# GaN_Driver.net
KiCad netlist of a schematic drawn in Altium Designer
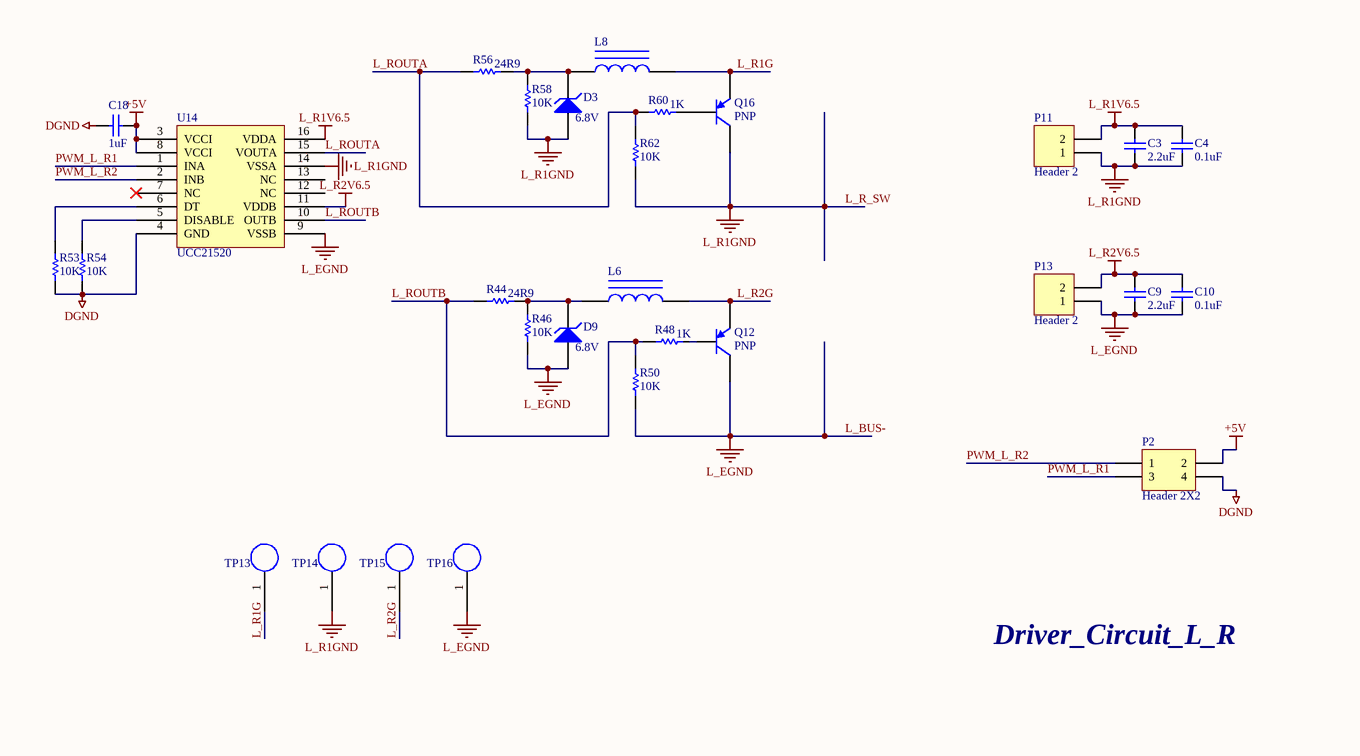
[diagram p0: GaN_Driver.SchDoc, left]

(export (version "E")
  (design (tool "Eeschema 10.0.6"))
  (components
    (comp (ref "C3")
      (value "2.2uF")
      (footprint "0603_C")
      (description "Capacitor")
      (fields
        (field (name "MANUFACTURER") "Generic Components")
        (field (name "PUBLISHER") "Altium Hobart Technology Centre")
      )
      (libsource (lib "Miscellaneous Devices") (part "Cap"))
    )
    (comp (ref "C4")
      (value "0.1uF")
      (footprint "0603_C")
      (description "Capacitor")
      (fields
        (field (name "MANUFACTURER") "Generic Components")
        (field (name "PUBLISHER") "Altium Hobart Technology Centre")
      )
      (libsource (lib "Miscellaneous Devices") (part "Cap"))
    )
    (comp (ref "C9")
      (value "2.2uF")
      (footprint "0603_C")
      (description "Capacitor")
      (fields
        (field (name "MANUFACTURER") "Generic Components")
        (field (name "PUBLISHER") "Altium Hobart Technology Centre")
      )
      (libsource (lib "Miscellaneous Devices") (part "Cap"))
    )
    (comp (ref "C10")
      (value "0.1uF")
      (footprint "0603_C")
      (description "Capacitor")
      (fields
        (field (name "MANUFACTURER") "Generic Components")
        (field (name "PUBLISHER") "Altium Hobart Technology Centre")
      )
      (libsource (lib "Miscellaneous Devices") (part "Cap"))
    )
    (comp (ref "C18")
      (value "1uF")
      (footprint "0603_C")
      (description "Capacitor")
      (fields
        (field (name "MANUFACTURER") "Generic Components")
        (field (name "PUBLISHER") "Altium Hobart Technology Centre")
      )
      (libsource (lib "Miscellaneous Devices") (part "Cap"))
    )
    (comp (ref "D3")
      (value "6.8V")
      (footprint "SOD323")
      (description "Zener Diode")
      (fields (field (name "PUBLISHER") "Altium Limited"))
      (libsource (lib "Miscellaneous Devices") (part "D Zener"))
    )
    (comp (ref "D9")
      (value "6.8V")
      (footprint "SOD323")
      (description "Zener Diode")
      (fields (field (name "PUBLISHER") "Altium Limited"))
      (libsource (lib "Miscellaneous Devices") (part "D Zener"))
    )
    (comp (ref "L6")
      (value "Inductor Iron")
      (footprint "0603_R")
      (description "Magnetic-Core Inductor")
      (fields (field (name "PUBLISHER") "Altium Limited"))
      (libsource (lib "Miscellaneous Devices") (part "Inductor Iron"))
    )
    (comp (ref "L8")
      (value "Inductor Iron")
      (footprint "0603_R")
      (description "Magnetic-Core Inductor")
      (fields (field (name "PUBLISHER") "Altium Limited"))
      (libsource (lib "Miscellaneous Devices") (part "Inductor Iron"))
    )
    (comp (ref "P2")
      (value "Header 2X2")
      (footprint "HDR2X2")
      (description "Header, 2-Pin, Dual row")
      (fields (field (name "PUBLISHER") "Altium Limited"))
      (libsource (lib "Miscellaneous Connectors") (part "Header 2X2"))
    )
    (comp (ref "P11")
      (value "Header 2")
      (footprint "HDR1X2")
      (description "Header, 2-Pin")
      (fields (field (name "PUBLISHER") "Altium Limited"))
      (libsource (lib "Miscellaneous Connectors") (part "Header 2"))
    )
    (comp (ref "P13")
      (value "Header 2")
      (footprint "HDR1X2")
      (description "Header, 2-Pin")
      (fields (field (name "PUBLISHER") "Altium Limited"))
      (libsource (lib "Miscellaneous Connectors") (part "Header 2"))
    )
    (comp (ref "Q12")
      (value "PNP")
      (footprint "SOT-23 (NPN/PNP)")
      (description "PNP Bipolar Transistor")
      (fields (field (name "PUBLISHER") "Altium Limited"))
      (libsource (lib "Miscellaneous Devices") (part "PNP"))
    )
    (comp (ref "Q16")
      (value "PNP")
      (footprint "SOT-23 (NPN/PNP)")
      (description "PNP Bipolar Transistor")
      (fields (field (name "PUBLISHER") "Altium Limited"))
      (libsource (lib "Miscellaneous Devices") (part "PNP"))
    )
    (comp (ref "R44")
      (value "24R9")
      (footprint "0603_R")
      (description "Semiconductor Resistor")
      (fields (field (name "PUBLISHER") "Altium Limited"))
      (libsource (lib "Miscellaneous Devices") (part "Res Semi"))
    )
    (comp (ref "R46")
      (value "10K")
      (footprint "0603_R")
      (description "Semiconductor Resistor")
      (fields (field (name "PUBLISHER") "Altium Limited"))
      (libsource (lib "Miscellaneous Devices") (part "Res Semi"))
    )
    (comp (ref "R48")
      (value "1K")
      (footprint "0603_R")
      (description "Semiconductor Resistor")
      (fields (field (name "Comment") "1k") (field (name "PUBLISHER") "Altium Limited"))
      (libsource (lib "Miscellaneous Devices") (part "Res Semi"))
    )
    (comp (ref "R50")
      (value "10K")
      (footprint "0603_R")
      (description "Semiconductor Resistor")
      (fields (field (name "PUBLISHER") "Altium Limited"))
      (libsource (lib "Miscellaneous Devices") (part "Res Semi"))
    )
    (comp (ref "R53")
      (value "10K")
      (footprint "0603_R")
      (description "Semiconductor Resistor")
      (fields (field (name "PUBLISHER") "Altium Limited"))
      (libsource (lib "Miscellaneous Devices") (part "Res Semi"))
    )
    (comp (ref "R54")
      (value "10K")
      (footprint "0603_R")
      (description "Semiconductor Resistor")
      (fields (field (name "PUBLISHER") "Altium Limited"))
      (libsource (lib "Miscellaneous Devices") (part "Res Semi"))
    )
    (comp (ref "R56")
      (value "24R9")
      (footprint "0603_R")
      (description "Semiconductor Resistor")
      (fields (field (name "PUBLISHER") "Altium Limited"))
      (libsource (lib "Miscellaneous Devices") (part "Res Semi"))
    )
    (comp (ref "R58")
      (value "10K")
      (footprint "0603_R")
      (description "Semiconductor Resistor")
      (fields (field (name "PUBLISHER") "Altium Limited"))
      (libsource (lib "Miscellaneous Devices") (part "Res Semi"))
    )
    (comp (ref "R60")
      (value "1K")
      (footprint "0603_R")
      (description "Semiconductor Resistor")
      (fields (field (name "Comment") "1k") (field (name "PUBLISHER") "Altium Limited"))
      (libsource (lib "Miscellaneous Devices") (part "Res Semi"))
    )
    (comp (ref "R62")
      (value "10K")
      (footprint "0603_R")
      (description "Semiconductor Resistor")
      (fields (field (name "PUBLISHER") "Altium Limited"))
      (libsource (lib "Miscellaneous Devices") (part "Res Semi"))
    )
    (comp (ref "TP13")
      (value "Test_Point")
      (footprint "Test_Point")
      (libsource (lib "GaN_Half_Bridge") (part "Test_Point"))
    )
    (comp (ref "TP14")
      (value "Test_Point")
      (footprint "Test_Point")
      (libsource (lib "GaN_Half_Bridge") (part "Test_Point"))
    )
    (comp (ref "TP15")
      (value "Test_Point")
      (footprint "Test_Point")
      (libsource (lib "GaN_Half_Bridge") (part "Test_Point"))
    )
    (comp (ref "TP16")
      (value "Test_Point")
      (footprint "Test_Point")
      (libsource (lib "GaN_Half_Bridge") (part "Test_Point"))
    )
    (comp (ref "U14")
      (value "UCC21520")
      (footprint "SOIC-16W")
      (libsource (lib "Schlib_LZW") (part "UCC21520"))
    )
  )
  (nets
    (net (code "1") (name "+5V") (class "Default")
      (node (ref "C18") (pin "1") (pinfunction "1_1") (pintype "passive"))
      (node (ref "P2") (pin "2") (pinfunction "2_2") (pintype "passive"))
      (node (ref "U14") (pin "3") (pinfunction "VCCI_3") (pintype "passive"))
      (node (ref "U14") (pin "8") (pinfunction "VCCI_8") (pintype "passive"))
    )
    (net (code "2") (name "/L_R1G") (class "Default")
      (node (ref "L8") (pin "2") (pinfunction "2_2") (pintype "passive"))
      (node (ref "Q16") (pin "3") (pinfunction "E_3") (pintype "passive"))
      (node (ref "TP13") (pin "1") (pinfunction "1_1") (pintype "passive"))
    )
    (net (code "3") (name "/L_R2G") (class "Default")
      (node (ref "L6") (pin "2") (pinfunction "2_2") (pintype "passive"))
      (node (ref "Q12") (pin "3") (pinfunction "E_3") (pintype "passive"))
      (node (ref "TP15") (pin "1") (pinfunction "1_1") (pintype "passive"))
    )
    (net (code "4") (name "/L_ROUTA") (class "Default")
      (node (ref "R56") (pin "1") (pinfunction "1_1") (pintype "passive"))
      (node (ref "R60") (pin "1") (pinfunction "1_1") (pintype "passive"))
      (node (ref "R62") (pin "2") (pinfunction "2_2") (pintype "passive"))
      (node (ref "U14") (pin "15") (pinfunction "VOUTA_15") (pintype "passive"))
    )
    (net (code "5") (name "/L_ROUTB") (class "Default")
      (node (ref "R44") (pin "1") (pinfunction "1_1") (pintype "passive"))
      (node (ref "R48") (pin "1") (pinfunction "1_1") (pintype "passive"))
      (node (ref "R50") (pin "2") (pinfunction "2_2") (pintype "passive"))
      (node (ref "U14") (pin "10") (pinfunction "OUTB_10") (pintype "passive"))
    )
    (net (code "6") (name "/PWM_L_R1") (class "Default")
      (node (ref "P2") (pin "3") (pinfunction "3_3") (pintype "passive"))
      (node (ref "U14") (pin "1") (pinfunction "INA_1") (pintype "passive"))
    )
    (net (code "7") (name "/PWM_L_R2") (class "Default")
      (node (ref "P2") (pin "1") (pinfunction "1_1") (pintype "passive"))
      (node (ref "U14") (pin "2") (pinfunction "INB_2") (pintype "passive"))
    )
    (net (code "8") (name "DGND") (class "Default")
      (node (ref "C18") (pin "2") (pinfunction "2_2") (pintype "passive"))
      (node (ref "P2") (pin "4") (pinfunction "4_4") (pintype "passive"))
      (node (ref "R53") (pin "1") (pinfunction "1_1") (pintype "passive"))
      (node (ref "R54") (pin "1") (pinfunction "1_1") (pintype "passive"))
      (node (ref "U14") (pin "4") (pinfunction "GND_4") (pintype "passive"))
    )
    (net (code "9") (name "L_EGND") (class "Default")
      (node (ref "C10") (pin "2") (pinfunction "2_2") (pintype "passive"))
      (node (ref "C9") (pin "2") (pinfunction "2_2") (pintype "passive"))
      (node (ref "D9") (pin "1") (pinfunction "A_1") (pintype "passive"))
      (node (ref "P13") (pin "1") (pinfunction "1_1") (pintype "passive"))
      (node (ref "Q12") (pin "1") (pinfunction "C_1") (pintype "passive"))
      (node (ref "R46") (pin "1") (pinfunction "1_1") (pintype "passive"))
      (node (ref "R50") (pin "1") (pinfunction "1_1") (pintype "passive"))
      (node (ref "TP16") (pin "1") (pinfunction "1_1") (pintype "passive"))
      (node (ref "U14") (pin "9") (pinfunction "VSSB_9") (pintype "passive"))
    )
    (net (code "10") (name "L_R1GND") (class "Default")
      (node (ref "C3") (pin "2") (pinfunction "2_2") (pintype "passive"))
      (node (ref "C4") (pin "2") (pinfunction "2_2") (pintype "passive"))
      (node (ref "D3") (pin "1") (pinfunction "A_1") (pintype "passive"))
      (node (ref "P11") (pin "1") (pinfunction "1_1") (pintype "passive"))
      (node (ref "Q16") (pin "1") (pinfunction "C_1") (pintype "passive"))
      (node (ref "R58") (pin "1") (pinfunction "1_1") (pintype "passive"))
      (node (ref "R62") (pin "1") (pinfunction "1_1") (pintype "passive"))
      (node (ref "TP14") (pin "1") (pinfunction "1_1") (pintype "passive"))
      (node (ref "U14") (pin "14") (pinfunction "VSSA_14") (pintype "passive"))
    )
    (net (code "11") (name "L_R1V6.5") (class "Default")
      (node (ref "C3") (pin "1") (pinfunction "1_1") (pintype "passive"))
      (node (ref "C4") (pin "1") (pinfunction "1_1") (pintype "passive"))
      (node (ref "P11") (pin "2") (pinfunction "2_2") (pintype "passive"))
      (node (ref "U14") (pin "16") (pinfunction "VDDA_16") (pintype "passive"))
    )
    (net (code "12") (name "L_R2V6.5") (class "Default")
      (node (ref "C10") (pin "1") (pinfunction "1_1") (pintype "passive"))
      (node (ref "C9") (pin "1") (pinfunction "1_1") (pintype "passive"))
      (node (ref "P13") (pin "2") (pinfunction "2_2") (pintype "passive"))
      (node (ref "U14") (pin "11") (pinfunction "VDDB_11") (pintype "passive"))
    )
    (net (code "13") (name "Net-(D3-K)") (class "Default")
      (node (ref "D3") (pin "2") (pinfunction "K_2") (pintype "passive"))
      (node (ref "L8") (pin "1") (pinfunction "1_1") (pintype "passive"))
      (node (ref "R56") (pin "2") (pinfunction "2_2") (pintype "passive"))
      (node (ref "R58") (pin "2") (pinfunction "2_2") (pintype "passive"))
    )
    (net (code "14") (name "Net-(D9-K)") (class "Default")
      (node (ref "D9") (pin "2") (pinfunction "K_2") (pintype "passive"))
      (node (ref "L6") (pin "1") (pinfunction "1_1") (pintype "passive"))
      (node (ref "R44") (pin "2") (pinfunction "2_2") (pintype "passive"))
      (node (ref "R46") (pin "2") (pinfunction "2_2") (pintype "passive"))
    )
    (net (code "15") (name "Net-(Q12-B)") (class "Default")
      (node (ref "Q12") (pin "2") (pinfunction "B_2") (pintype "passive"))
      (node (ref "R48") (pin "2") (pinfunction "2_2") (pintype "passive"))
    )
    (net (code "16") (name "Net-(Q16-B)") (class "Default")
      (node (ref "Q16") (pin "2") (pinfunction "B_2") (pintype "passive"))
      (node (ref "R60") (pin "2") (pinfunction "2_2") (pintype "passive"))
    )
    (net (code "17") (name "Net-(U14-DISABLE)") (class "Default")
      (node (ref "R54") (pin "2") (pinfunction "2_2") (pintype "passive"))
      (node (ref "U14") (pin "5") (pinfunction "DISABLE_5") (pintype "passive"))
    )
    (net (code "18") (name "Net-(U14-DT)") (class "Default")
      (node (ref "R53") (pin "2") (pinfunction "2_2") (pintype "passive"))
      (node (ref "U14") (pin "6") (pinfunction "DT_6") (pintype "passive"))
    )
    (net (code "19") (name "unconnected-(U14-NC-Pad7)") (class "Default")
      (node (ref "U14") (pin "7") (pinfunction "NC_7") (pintype "passive+no_connect"))
    )
    (net (code "20") (name "unconnected-(U14-NC-Pad12)") (class "Default")
      (node (ref "U14") (pin "12") (pinfunction "NC_12") (pintype "passive"))
    )
    (net (code "21") (name "unconnected-(U14-NC-Pad13)") (class "Default")
      (node (ref "U14") (pin "13") (pinfunction "NC_13") (pintype "passive"))
    )
  )
)
